# SCH_RP2040_2022-08-20.net
KiCad netlist of a schematic drawn in Altium Designer
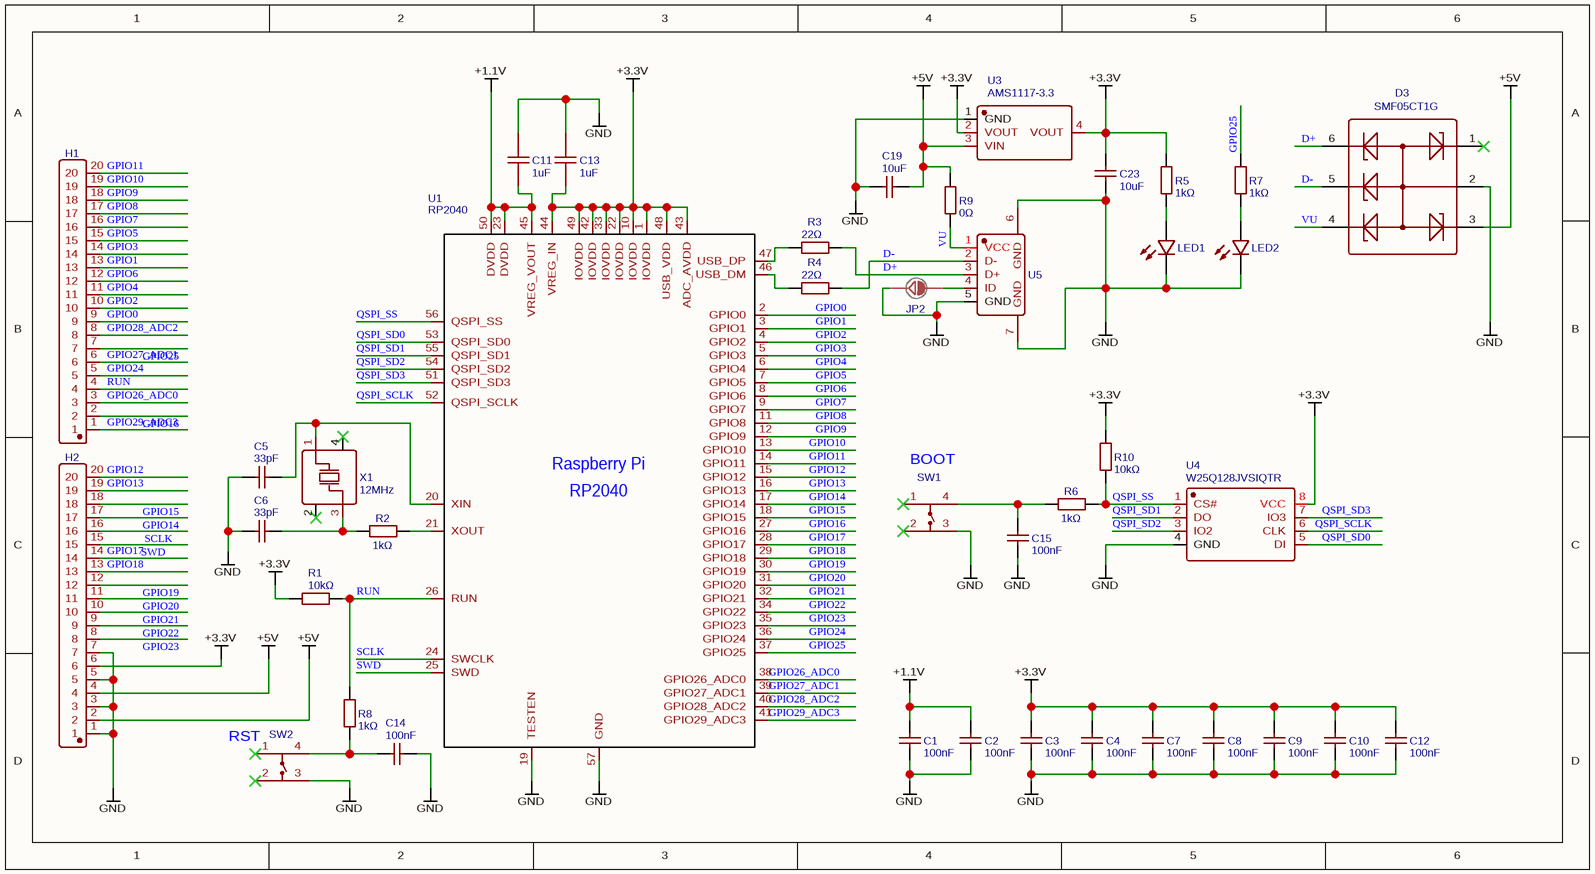
[diagram p0: SCH_RP2040_2022-08-20.schdoc]

(export (version "E")
  (design (tool "Eeschema 10.0.6"))
  (components
    (comp (ref "C1")
      (value "100nF")
      (fields
        (field (name "BOM_MANUFACTURER PART") "CL05B104KO5NNNC")
        (field (name "BOM_SUPPLIER PART") "C1525")
      )
      (libsource (lib "altium-import") (part "root_1_100nF_"))
    )
    (comp (ref "C2")
      (value "100nF")
      (fields
        (field (name "BOM_MANUFACTURER PART") "CL05B104KO5NNNC")
        (field (name "BOM_SUPPLIER PART") "C1525")
      )
      (libsource (lib "altium-import") (part "root_1_100nF_"))
    )
    (comp (ref "C3")
      (value "100nF")
      (fields
        (field (name "BOM_MANUFACTURER PART") "CL05B104KO5NNNC")
        (field (name "BOM_SUPPLIER PART") "C1525")
      )
      (libsource (lib "altium-import") (part "root_1_100nF_"))
    )
    (comp (ref "C4")
      (value "100nF")
      (fields
        (field (name "BOM_MANUFACTURER PART") "CL05B104KO5NNNC")
        (field (name "BOM_SUPPLIER PART") "C1525")
      )
      (libsource (lib "altium-import") (part "root_1_100nF_"))
    )
    (comp (ref "C5")
      (value "33pF")
      (fields
        (field (name "BOM_MANUFACTURER PART") "0402CG330J500NT")
        (field (name "BOM_SUPPLIER PART") "C1562")
      )
      (libsource (lib "altium-import") (part "root_0_33pF_"))
    )
    (comp (ref "C6")
      (value "33pF")
      (fields
        (field (name "BOM_MANUFACTURER PART") "0402CG330J500NT")
        (field (name "BOM_SUPPLIER PART") "C1562")
      )
      (libsource (lib "altium-import") (part "root_0_33pF_"))
    )
    (comp (ref "C7")
      (value "100nF")
      (fields
        (field (name "BOM_MANUFACTURER PART") "CL05B104KO5NNNC")
        (field (name "BOM_SUPPLIER PART") "C1525")
      )
      (libsource (lib "altium-import") (part "root_1_100nF_"))
    )
    (comp (ref "C8")
      (value "100nF")
      (fields
        (field (name "BOM_MANUFACTURER PART") "CL05B104KO5NNNC")
        (field (name "BOM_SUPPLIER PART") "C1525")
      )
      (libsource (lib "altium-import") (part "root_1_100nF_"))
    )
    (comp (ref "C9")
      (value "100nF")
      (fields
        (field (name "BOM_MANUFACTURER PART") "CL05B104KO5NNNC")
        (field (name "BOM_SUPPLIER PART") "C1525")
      )
      (libsource (lib "altium-import") (part "root_1_100nF_"))
    )
    (comp (ref "C10")
      (value "100nF")
      (fields
        (field (name "BOM_MANUFACTURER PART") "CL05B104KO5NNNC")
        (field (name "BOM_SUPPLIER PART") "C1525")
      )
      (libsource (lib "altium-import") (part "root_1_100nF_"))
    )
    (comp (ref "C11")
      (value "1uF")
      (fields
        (field (name "BOM_MANUFACTURER PART") "CL05A105KA5NQNC")
        (field (name "BOM_SUPPLIER PART") "C52923")
      )
      (libsource (lib "altium-import") (part "root_1_1uF_"))
    )
    (comp (ref "C12")
      (value "100nF")
      (fields
        (field (name "BOM_MANUFACTURER PART") "CL05B104KO5NNNC")
        (field (name "BOM_SUPPLIER PART") "C1525")
      )
      (libsource (lib "altium-import") (part "root_1_100nF_"))
    )
    (comp (ref "C13")
      (value "1uF")
      (fields
        (field (name "BOM_MANUFACTURER PART") "CL05A105KA5NQNC")
        (field (name "BOM_SUPPLIER PART") "C52923")
      )
      (libsource (lib "altium-import") (part "root_1_1uF_"))
    )
    (comp (ref "C14")
      (value "100nF")
      (fields
        (field (name "BOM_MANUFACTURER PART") "CL05B104KO5NNNC")
        (field (name "BOM_SUPPLIER PART") "C1525")
      )
      (libsource (lib "altium-import") (part "root_2_100nF_"))
    )
    (comp (ref "C15")
      (value "100nF")
      (fields
        (field (name "BOM_MANUFACTURER PART") "CL05B104KO5NNNC")
        (field (name "BOM_SUPPLIER PART") "C1525")
      )
      (libsource (lib "altium-import") (part "root_1_100nF_"))
    )
    (comp (ref "C19")
      (value "10uF")
      (fields
        (field (name "BOM_MANUFACTURER PART") "CL31A106KBHNNNE")
        (field (name "BOM_SUPPLIER PART") "C13585")
      )
      (libsource (lib "altium-import") (part "root_0_10uF_"))
    )
    (comp (ref "C23")
      (value "10uF")
      (fields
        (field (name "BOM_MANUFACTURER PART") "CL31A106KBHNNNE")
        (field (name "BOM_SUPPLIER PART") "C13585")
      )
      (libsource (lib "altium-import") (part "root_1_10uF_"))
    )
    (comp (ref "D3")
      (value "SMF05CT1G")
      (fields (field (name "BOM_SUPPLIER PART") "C15879"))
      (libsource (lib "altium-import") (part "root_0_SMF05CT1G_"))
    )
    (comp (ref "H1")
      (value "KH-2.54PH180-1X20P-L11.5")
      (fields (field (name "BOM_SUPPLIER PART") "C2905493") (field (name "CONTRIBUTOR") "LCSC"))
      (libsource (lib "altium-import") (part "root_2_KH-2.54PH180-1X20P-L11.5_"))
    )
    (comp (ref "H2")
      (value "KH-2.54PH180-1X20P-L11.5")
      (fields (field (name "BOM_SUPPLIER PART") "C2905493") (field (name "CONTRIBUTOR") "LCSC"))
      (libsource (lib "altium-import") (part "root_2_KH-2.54PH180-1X20P-L11.5_"))
    )
    (comp (ref "JP2")
      (value "JUMPER-SMT_2")
      (fields (field (name "CONTRIBUTOR") "Celeron"))
      (libsource (lib "altium-import") (part "root_0_JUMPER-SMT_2_"))
    )
    (comp (ref "LED1")
      (value "19-217/BHC-ZL1M2RY/3T")
      (fields (field (name "BOM_SUPPLIER PART") "C72041"))
      (libsource (lib "altium-import") (part "root_1_19-217/BHC-ZL1M2RY/3T_"))
    )
    (comp (ref "LED2")
      (value "19-217/BHC-ZL1M2RY/3T")
      (fields (field (name "BOM_SUPPLIER PART") "C72041"))
      (libsource (lib "altium-import") (part "root_1_19-217/BHC-ZL1M2RY/3T_"))
    )
    (comp (ref "R1")
      (value "10kΩ")
      (fields
        (field (name "BOM_MANUFACTURER PART") "0402WGF1002TCE")
        (field (name "BOM_SUPPLIER PART") "C25744")
      )
      (libsource (lib "altium-import") (part "root_2_10kΩ_"))
    )
    (comp (ref "R2")
      (value "1kΩ")
      (fields
        (field (name "BOM_MANUFACTURER PART") "0402WGF1001TCE")
        (field (name "BOM_SUPPLIER PART") "C11702")
      )
      (libsource (lib "altium-import") (part "root_0_1kΩ_"))
    )
    (comp (ref "R3")
      (value "22Ω")
      (fields
        (field (name "BOM_MANUFACTURER PART") "0402WGF220JTCE")
        (field (name "BOM_SUPPLIER PART") "C25092")
      )
      (libsource (lib "altium-import") (part "root_0_22Ω_"))
    )
    (comp (ref "R4")
      (value "22Ω")
      (fields
        (field (name "BOM_MANUFACTURER PART") "0402WGF220JTCE")
        (field (name "BOM_SUPPLIER PART") "C25092")
      )
      (libsource (lib "altium-import") (part "root_0_22Ω_"))
    )
    (comp (ref "R5")
      (value "1kΩ")
      (fields
        (field (name "BOM_MANUFACTURER PART") "0402WGF1001TCE")
        (field (name "BOM_SUPPLIER PART") "C11702")
      )
      (libsource (lib "altium-import") (part "root_1_1kΩ_"))
    )
    (comp (ref "R6")
      (value "1kΩ")
      (fields
        (field (name "BOM_MANUFACTURER PART") "0402WGF1001TCE")
        (field (name "BOM_SUPPLIER PART") "C11702")
      )
      (libsource (lib "altium-import") (part "root_0_1kΩ_"))
    )
    (comp (ref "R7")
      (value "1kΩ")
      (fields
        (field (name "BOM_MANUFACTURER PART") "0402WGF1001TCE")
        (field (name "BOM_SUPPLIER PART") "C11702")
      )
      (libsource (lib "altium-import") (part "root_1_1kΩ_"))
    )
    (comp (ref "R8")
      (value "1kΩ")
      (fields
        (field (name "BOM_MANUFACTURER PART") "0402WGF1001TCE")
        (field (name "BOM_SUPPLIER PART") "C11702")
      )
      (libsource (lib "altium-import") (part "root_1_1kΩ_"))
    )
    (comp (ref "R9")
      (value "0Ω")
      (fields
        (field (name "BOM_MANUFACTURER PART") "0603WAF0000T5E")
        (field (name "BOM_SUPPLIER PART") "C21189")
      )
      (libsource (lib "altium-import") (part "root_1_0Ω_"))
    )
    (comp (ref "R10")
      (value "10kΩ")
      (fields
        (field (name "BOM_MANUFACTURER PART") "0402WGF1002TCE")
        (field (name "BOM_SUPPLIER PART") "C25744")
      )
      (libsource (lib "altium-import") (part "root_1_10kΩ_"))
    )
    (comp (ref "SW1")
      (value "TD-1182SA-2.0H-250")
      (fields (field (name "BOM_SUPPLIER PART") "C2905178") (field (name "CONTRIBUTOR") "LCSC"))
      (libsource (lib "altium-import") (part "root_0_TD-1182SA-2.0H-250_"))
    )
    (comp (ref "SW2")
      (value "TD-1182SA-2.0H-250")
      (fields (field (name "BOM_SUPPLIER PART") "C2905178") (field (name "CONTRIBUTOR") "LCSC"))
      (libsource (lib "altium-import") (part "root_0_TD-1182SA-2.0H-250_"))
    )
    (comp (ref "U1")
      (value "RP2040")
      (fields (field (name "BOM_SUPPLIER PART") "C2040") (field (name "CONTRIBUTOR") "LCSC"))
      (libsource (lib "altium-import") (part "root_0_RP2040_"))
    )
    (comp (ref "U3")
      (value "AMS1117-3.3")
      (fields (field (name "BOM_SUPPLIER PART") "C6186"))
      (libsource (lib "altium-import") (part "root_0_AMS1117-3.3_"))
    )
    (comp (ref "U4")
      (value "W25Q128JVSIQTR")
      (fields (field (name "BOM_SUPPLIER PART") "C97521"))
      (libsource (lib "altium-import") (part "root_0_W25Q128JVSIQTR_"))
    )
    (comp (ref "U5")
      (value "U253-051N-4BH89-S2S")
      (fields (field (name "BOM_SUPPLIER PART") "C2880620") (field (name "CONTRIBUTOR") "LCSC"))
      (libsource (lib "altium-import") (part "root_0_U253-051N-4BH89-S2S_"))
    )
    (comp (ref "X1")
      (value "12MHz")
      (fields
        (field (name "BOM_MANUFACTURER PART") "X322512MSB4SI")
        (field (name "BOM_SUPPLIER PART") "C9002")
      )
      (libsource (lib "altium-import") (part "root_3_12MHz_"))
    )
  )
  (nets
    (net (code "1") (name "+1.1V") (class "Default")
      (node (ref "C1") (pin "2") (pinfunction "2_2") (pintype "passive"))
      (node (ref "C11") (pin "1") (pinfunction "1_1") (pintype "passive"))
      (node (ref "C2") (pin "2") (pinfunction "2_2") (pintype "passive"))
      (node (ref "U1") (pin "23") (pinfunction "DVDD_23") (pintype "passive"))
      (node (ref "U1") (pin "45") (pinfunction "VREG_VOUT_45") (pintype "passive"))
      (node (ref "U1") (pin "50") (pinfunction "DVDD_50") (pintype "passive"))
    )
    (net (code "2") (name "+3.3V") (class "Default")
      (node (ref "C10") (pin "2") (pinfunction "2_2") (pintype "passive"))
      (node (ref "C12") (pin "2") (pinfunction "2_2") (pintype "passive"))
      (node (ref "C13") (pin "1") (pinfunction "1_1") (pintype "passive"))
      (node (ref "C23") (pin "2") (pinfunction "2_2") (pintype "passive"))
      (node (ref "C3") (pin "2") (pinfunction "2_2") (pintype "passive"))
      (node (ref "C4") (pin "2") (pinfunction "2_2") (pintype "passive"))
      (node (ref "C7") (pin "2") (pinfunction "2_2") (pintype "passive"))
      (node (ref "C8") (pin "2") (pinfunction "2_2") (pintype "passive"))
      (node (ref "C9") (pin "2") (pinfunction "2_2") (pintype "passive"))
      (node (ref "H2") (pin "6") (pinfunction "6_6") (pintype "passive"))
      (node (ref "R1") (pin "2") (pinfunction "2_2") (pintype "passive"))
      (node (ref "R10") (pin "2") (pinfunction "2_2") (pintype "passive"))
      (node (ref "R5") (pin "2") (pinfunction "2_2") (pintype "passive"))
      (node (ref "U1") (pin "1") (pinfunction "IOVDD_1") (pintype "passive"))
      (node (ref "U1") (pin "10") (pinfunction "IOVDD_10") (pintype "passive"))
      (node (ref "U1") (pin "22") (pinfunction "IOVDD_22") (pintype "passive"))
      (node (ref "U1") (pin "33") (pinfunction "IOVDD_33") (pintype "passive"))
      (node (ref "U1") (pin "42") (pinfunction "IOVDD_42") (pintype "passive"))
      (node (ref "U1") (pin "43") (pinfunction "ADC_AVDD_43") (pintype "passive"))
      (node (ref "U1") (pin "44") (pinfunction "VREG_IN_44") (pintype "passive"))
      (node (ref "U1") (pin "48") (pinfunction "USB_VDD_48") (pintype "passive"))
      (node (ref "U1") (pin "49") (pinfunction "IOVDD_49") (pintype "passive"))
      (node (ref "U3") (pin "2") (pinfunction "VOUT_2") (pintype "passive"))
      (node (ref "U3") (pin "4") (pinfunction "VOUT_4") (pintype "passive"))
      (node (ref "U4") (pin "8") (pinfunction "VCC_8") (pintype "passive"))
    )
    (net (code "3") (name "+5V") (class "Default")
      (node (ref "C19") (pin "2") (pinfunction "2_2") (pintype "passive"))
      (node (ref "D3") (pin "3") (pinfunction "3_3") (pintype "passive"))
      (node (ref "H2") (pin "2") (pinfunction "2_2") (pintype "passive"))
      (node (ref "H2") (pin "4") (pinfunction "4_4") (pintype "passive"))
      (node (ref "R9") (pin "2") (pinfunction "2_2") (pintype "passive"))
      (node (ref "U3") (pin "3") (pinfunction "VIN_3") (pintype "passive"))
    )
    (net (code "4") (name "/D+") (class "Default")
      (node (ref "D3") (pin "6") (pinfunction "6_6") (pintype "passive"))
      (node (ref "R3") (pin "1") (pinfunction "1_1") (pintype "passive"))
      (node (ref "U5") (pin "3") (pinfunction "D+_3") (pintype "passive"))
    )
    (net (code "5") (name "/D-") (class "Default")
      (node (ref "D3") (pin "5") (pinfunction "5_5") (pintype "passive"))
      (node (ref "R4") (pin "1") (pinfunction "1_1") (pintype "passive"))
      (node (ref "U5") (pin "2") (pinfunction "D-_2") (pintype "passive"))
    )
    (net (code "6") (name "/GPIO0") (class "Default")
      (node (ref "H1") (pin "9") (pinfunction "9_9") (pintype "passive"))
      (node (ref "U1") (pin "2") (pinfunction "GPIO0_2") (pintype "passive"))
    )
    (net (code "7") (name "/GPIO1") (class "Default")
      (node (ref "H1") (pin "13") (pinfunction "13_13") (pintype "passive"))
      (node (ref "U1") (pin "3") (pinfunction "GPIO1_3") (pintype "passive"))
    )
    (net (code "8") (name "/GPIO2") (class "Default")
      (node (ref "H1") (pin "10") (pinfunction "10_10") (pintype "passive"))
      (node (ref "U1") (pin "4") (pinfunction "GPIO2_4") (pintype "passive"))
    )
    (net (code "9") (name "/GPIO3") (class "Default")
      (node (ref "H1") (pin "14") (pinfunction "14_14") (pintype "passive"))
      (node (ref "U1") (pin "5") (pinfunction "GPIO3_5") (pintype "passive"))
    )
    (net (code "10") (name "/GPIO4") (class "Default")
      (node (ref "H1") (pin "11") (pinfunction "11_11") (pintype "passive"))
      (node (ref "U1") (pin "6") (pinfunction "GPIO4_6") (pintype "passive"))
    )
    (net (code "11") (name "/GPIO5") (class "Default")
      (node (ref "H1") (pin "15") (pinfunction "15_15") (pintype "passive"))
      (node (ref "U1") (pin "7") (pinfunction "GPIO5_7") (pintype "passive"))
    )
    (net (code "12") (name "/GPIO6") (class "Default")
      (node (ref "H1") (pin "12") (pinfunction "12_12") (pintype "passive"))
      (node (ref "U1") (pin "8") (pinfunction "GPIO6_8") (pintype "passive"))
    )
    (net (code "13") (name "/GPIO7") (class "Default")
      (node (ref "H1") (pin "16") (pinfunction "16_16") (pintype "passive"))
      (node (ref "U1") (pin "9") (pinfunction "GPIO7_9") (pintype "passive"))
    )
    (net (code "14") (name "/GPIO8") (class "Default")
      (node (ref "H1") (pin "17") (pinfunction "17_17") (pintype "passive"))
      (node (ref "U1") (pin "11") (pinfunction "GPIO8_11") (pintype "passive"))
    )
    (net (code "15") (name "/GPIO9") (class "Default")
      (node (ref "H1") (pin "18") (pinfunction "18_18") (pintype "passive"))
      (node (ref "U1") (pin "12") (pinfunction "GPIO9_12") (pintype "passive"))
    )
    (net (code "16") (name "/GPIO10") (class "Default")
      (node (ref "H1") (pin "19") (pinfunction "19_19") (pintype "passive"))
      (node (ref "U1") (pin "13") (pinfunction "GPIO10_13") (pintype "passive"))
    )
    (net (code "17") (name "/GPIO11") (class "Default")
      (node (ref "H1") (pin "20") (pinfunction "20_20") (pintype "passive"))
      (node (ref "U1") (pin "14") (pinfunction "GPIO11_14") (pintype "passive"))
    )
    (net (code "18") (name "/GPIO12") (class "Default")
      (node (ref "H2") (pin "20") (pinfunction "20_20") (pintype "passive"))
      (node (ref "U1") (pin "15") (pinfunction "GPIO12_15") (pintype "passive"))
    )
    (net (code "19") (name "/GPIO13") (class "Default")
      (node (ref "H2") (pin "19") (pinfunction "19_19") (pintype "passive"))
      (node (ref "U1") (pin "16") (pinfunction "GPIO13_16") (pintype "passive"))
    )
    (net (code "20") (name "/GPIO14") (class "Default")
      (node (ref "H2") (pin "17") (pinfunction "17_17") (pintype "passive"))
      (node (ref "U1") (pin "17") (pinfunction "GPIO14_17") (pintype "passive"))
    )
    (net (code "21") (name "/GPIO15") (class "Default")
      (node (ref "H2") (pin "18") (pinfunction "18_18") (pintype "passive"))
      (node (ref "U1") (pin "18") (pinfunction "GPIO15_18") (pintype "passive"))
    )
    (net (code "22") (name "/GPIO16") (class "Default")
      (node (ref "H1") (pin "2") (pinfunction "2_2") (pintype "passive"))
      (node (ref "U1") (pin "27") (pinfunction "GPIO16_27") (pintype "passive"))
    )
    (net (code "23") (name "/GPIO17") (class "Default")
      (node (ref "H2") (pin "14") (pinfunction "14_14") (pintype "passive"))
      (node (ref "U1") (pin "28") (pinfunction "GPIO17_28") (pintype "passive"))
    )
    (net (code "24") (name "/GPIO18") (class "Default")
      (node (ref "H2") (pin "13") (pinfunction "13_13") (pintype "passive"))
      (node (ref "U1") (pin "29") (pinfunction "GPIO18_29") (pintype "passive"))
    )
    (net (code "25") (name "/GPIO19") (class "Default")
      (node (ref "H2") (pin "12") (pinfunction "12_12") (pintype "passive"))
      (node (ref "U1") (pin "30") (pinfunction "GPIO19_30") (pintype "passive"))
    )
    (net (code "26") (name "/GPIO20") (class "Default")
      (node (ref "H2") (pin "11") (pinfunction "11_11") (pintype "passive"))
      (node (ref "U1") (pin "31") (pinfunction "GPIO20_31") (pintype "passive"))
    )
    (net (code "27") (name "/GPIO21") (class "Default")
      (node (ref "H2") (pin "10") (pinfunction "10_10") (pintype "passive"))
      (node (ref "U1") (pin "32") (pinfunction "GPIO21_32") (pintype "passive"))
    )
    (net (code "28") (name "/GPIO22") (class "Default")
      (node (ref "H2") (pin "9") (pinfunction "9_9") (pintype "passive"))
      (node (ref "U1") (pin "34") (pinfunction "GPIO22_34") (pintype "passive"))
    )
    (net (code "29") (name "/GPIO23") (class "Default")
      (node (ref "H2") (pin "8") (pinfunction "8_8") (pintype "passive"))
      (node (ref "U1") (pin "35") (pinfunction "GPIO23_35") (pintype "passive"))
    )
    (net (code "30") (name "/GPIO24") (class "Default")
      (node (ref "H1") (pin "5") (pinfunction "5_5") (pintype "passive"))
      (node (ref "U1") (pin "36") (pinfunction "GPIO24_36") (pintype "passive"))
    )
    (net (code "31") (name "/GPIO25") (class "Default")
      (node (ref "H1") (pin "7") (pinfunction "7_7") (pintype "passive"))
      (node (ref "R7") (pin "2") (pinfunction "2_2") (pintype "passive"))
      (node (ref "U1") (pin "37") (pinfunction "GPIO25_37") (pintype "passive"))
    )
    (net (code "32") (name "/GPIO26_ADC0") (class "Default")
      (node (ref "H1") (pin "3") (pinfunction "3_3") (pintype "passive"))
      (node (ref "U1") (pin "38") (pinfunction "GPIO26_ADC0_38") (pintype "passive"))
    )
    (net (code "33") (name "/GPIO27_ADC1") (class "Default")
      (node (ref "H1") (pin "6") (pinfunction "6_6") (pintype "passive"))
      (node (ref "U1") (pin "39") (pinfunction "GPIO27_ADC1_39") (pintype "passive"))
    )
    (net (code "34") (name "/GPIO28_ADC2") (class "Default")
      (node (ref "H1") (pin "8") (pinfunction "8_8") (pintype "passive"))
      (node (ref "U1") (pin "40") (pinfunction "GPIO28_ADC2_40") (pintype "passive"))
    )
    (net (code "35") (name "/GPIO29_ADC3") (class "Default")
      (node (ref "H1") (pin "1") (pinfunction "1_1") (pintype "passive"))
      (node (ref "U1") (pin "41") (pinfunction "GPIO29_ADC3_41") (pintype "passive"))
    )
    (net (code "36") (name "/QSPI_SCLK") (class "Default")
      (node (ref "U1") (pin "52") (pinfunction "QSPI_SCLK_52") (pintype "passive"))
      (node (ref "U4") (pin "6") (pinfunction "CLK_6") (pintype "passive"))
    )
    (net (code "37") (name "/QSPI_SD0") (class "Default")
      (node (ref "U1") (pin "53") (pinfunction "QSPI_SD0_53") (pintype "passive"))
      (node (ref "U4") (pin "5") (pinfunction "DI_5") (pintype "passive"))
    )
    (net (code "38") (name "/QSPI_SD1") (class "Default")
      (node (ref "U1") (pin "55") (pinfunction "QSPI_SD1_55") (pintype "passive"))
      (node (ref "U4") (pin "2") (pinfunction "DO_2") (pintype "passive"))
    )
    (net (code "39") (name "/QSPI_SD2") (class "Default")
      (node (ref "U1") (pin "54") (pinfunction "QSPI_SD2_54") (pintype "passive"))
      (node (ref "U4") (pin "3") (pinfunction "IO2_3") (pintype "passive"))
    )
    (net (code "40") (name "/QSPI_SD3") (class "Default")
      (node (ref "U1") (pin "51") (pinfunction "QSPI_SD3_51") (pintype "passive"))
      (node (ref "U4") (pin "7") (pinfunction "IO3_7") (pintype "passive"))
    )
    (net (code "41") (name "/QSPI_SS") (class "Default")
      (node (ref "R10") (pin "1") (pinfunction "1_1") (pintype "passive"))
      (node (ref "R6") (pin "2") (pinfunction "2_2") (pintype "passive"))
      (node (ref "U1") (pin "56") (pinfunction "QSPI_SS_56") (pintype "passive"))
      (node (ref "U4") (pin "1") (pinfunction "CS#_1") (pintype "passive"))
    )
    (net (code "42") (name "/RUN") (class "Default")
      (node (ref "H1") (pin "4") (pinfunction "4_4") (pintype "passive"))
      (node (ref "R1") (pin "1") (pinfunction "1_1") (pintype "passive"))
      (node (ref "R8") (pin "2") (pinfunction "2_2") (pintype "passive"))
      (node (ref "U1") (pin "26") (pinfunction "RUN_26") (pintype "passive"))
    )
    (net (code "43") (name "/SCLK") (class "Default")
      (node (ref "H2") (pin "16") (pinfunction "16_16") (pintype "passive"))
      (node (ref "U1") (pin "24") (pinfunction "SWCLK_24") (pintype "passive"))
    )
    (net (code "44") (name "/SWD") (class "Default")
      (node (ref "H2") (pin "15") (pinfunction "15_15") (pintype "passive"))
      (node (ref "U1") (pin "25") (pinfunction "SWD_25") (pintype "passive"))
    )
    (net (code "45") (name "/VU") (class "Default")
      (node (ref "D3") (pin "4") (pinfunction "4_4") (pintype "passive"))
      (node (ref "R9") (pin "1") (pinfunction "1_1") (pintype "passive"))
      (node (ref "U5") (pin "1") (pinfunction "VCC_1") (pintype "passive"))
    )
    (net (code "46") (name "GND") (class "Default")
      (node (ref "C1") (pin "1") (pinfunction "1_1") (pintype "passive"))
      (node (ref "C10") (pin "1") (pinfunction "1_1") (pintype "passive"))
      (node (ref "C11") (pin "2") (pinfunction "2_2") (pintype "passive"))
      (node (ref "C12") (pin "1") (pinfunction "1_1") (pintype "passive"))
      (node (ref "C13") (pin "2") (pinfunction "2_2") (pintype "passive"))
      (node (ref "C14") (pin "1") (pinfunction "1_1") (pintype "passive"))
      (node (ref "C15") (pin "1") (pinfunction "1_1") (pintype "passive"))
      (node (ref "C19") (pin "1") (pinfunction "1_1") (pintype "passive"))
      (node (ref "C2") (pin "1") (pinfunction "1_1") (pintype "passive"))
      (node (ref "C23") (pin "1") (pinfunction "1_1") (pintype "passive"))
      (node (ref "C3") (pin "1") (pinfunction "1_1") (pintype "passive"))
      (node (ref "C4") (pin "1") (pinfunction "1_1") (pintype "passive"))
      (node (ref "C5") (pin "1") (pinfunction "1_1") (pintype "passive"))
      (node (ref "C6") (pin "1") (pinfunction "1_1") (pintype "passive"))
      (node (ref "C7") (pin "1") (pinfunction "1_1") (pintype "passive"))
      (node (ref "C8") (pin "1") (pinfunction "1_1") (pintype "passive"))
      (node (ref "C9") (pin "1") (pinfunction "1_1") (pintype "passive"))
      (node (ref "D3") (pin "2") (pinfunction "2_2") (pintype "passive"))
      (node (ref "H2") (pin "1") (pinfunction "1_1") (pintype "passive"))
      (node (ref "H2") (pin "3") (pinfunction "3_3") (pintype "passive"))
      (node (ref "H2") (pin "5") (pinfunction "5_5") (pintype "passive"))
      (node (ref "H2") (pin "7") (pinfunction "7_7") (pintype "passive"))
      (node (ref "JP2") (pin "1") (pinfunction "1_1") (pintype "passive"))
      (node (ref "LED1") (pin "2") (pinfunction "C_2") (pintype "passive"))
      (node (ref "LED2") (pin "2") (pinfunction "C_2") (pintype "passive"))
      (node (ref "SW1") (pin "3") (pinfunction "3_3") (pintype "passive"))
      (node (ref "SW2") (pin "3") (pinfunction "3_3") (pintype "passive"))
      (node (ref "U1") (pin "19") (pinfunction "TESTEN_19") (pintype "passive"))
      (node (ref "U1") (pin "57") (pinfunction "GND_57") (pintype "passive"))
      (node (ref "U3") (pin "1") (pinfunction "GND_1") (pintype "passive"))
      (node (ref "U4") (pin "4") (pinfunction "GND_4") (pintype "passive"))
      (node (ref "U5") (pin "5") (pinfunction "GND_5") (pintype "passive"))
      (node (ref "U5") (pin "6") (pinfunction "GND_6") (pintype "passive"))
      (node (ref "U5") (pin "7") (pinfunction "GND_7") (pintype "passive"))
    )
    (net (code "47") (name "Net-(C14-Pad2)") (class "Default")
      (node (ref "C14") (pin "2") (pinfunction "2_2") (pintype "passive"))
      (node (ref "R8") (pin "1") (pinfunction "1_1") (pintype "passive"))
      (node (ref "SW2") (pin "4") (pinfunction "4_4") (pintype "passive"))
    )
    (net (code "48") (name "Net-(C15-Pad2)") (class "Default")
      (node (ref "C15") (pin "2") (pinfunction "2_2") (pintype "passive"))
      (node (ref "R6") (pin "1") (pinfunction "1_1") (pintype "passive"))
      (node (ref "SW1") (pin "4") (pinfunction "4_4") (pintype "passive"))
    )
    (net (code "49") (name "Net-(LED1-A)") (class "Default")
      (node (ref "LED1") (pin "1") (pinfunction "A_1") (pintype "passive"))
      (node (ref "R5") (pin "1") (pinfunction "1_1") (pintype "passive"))
    )
    (net (code "50") (name "Net-(LED2-A)") (class "Default")
      (node (ref "LED2") (pin "1") (pinfunction "A_1") (pintype "passive"))
      (node (ref "R7") (pin "1") (pinfunction "1_1") (pintype "passive"))
    )
    (net (code "51") (name "Net-(U1-USB_DM)") (class "Default")
      (node (ref "R4") (pin "2") (pinfunction "2_2") (pintype "passive"))
      (node (ref "U1") (pin "46") (pinfunction "USB_DM_46") (pintype "passive"))
    )
    (net (code "52") (name "Net-(U1-USB_DP)") (class "Default")
      (node (ref "R3") (pin "2") (pinfunction "2_2") (pintype "passive"))
      (node (ref "U1") (pin "47") (pinfunction "USB_DP_47") (pintype "passive"))
    )
    (net (code "53") (name "Net-(U1-XIN)") (class "Default")
      (node (ref "C5") (pin "2") (pinfunction "2_2") (pintype "passive"))
      (node (ref "U1") (pin "20") (pinfunction "XIN_20") (pintype "passive"))
      (node (ref "X1") (pin "1") (pinfunction "OSC1_1") (pintype "passive"))
    )
    (net (code "54") (name "Net-(U1-XOUT)") (class "Default")
      (node (ref "R2") (pin "2") (pinfunction "2_2") (pintype "passive"))
      (node (ref "U1") (pin "21") (pinfunction "XOUT_21") (pintype "passive"))
    )
    (net (code "55") (name "Net-(U5-ID)") (class "Default")
      (node (ref "JP2") (pin "2") (pinfunction "2_2") (pintype "passive"))
      (node (ref "U5") (pin "4") (pinfunction "ID_4") (pintype "passive"))
    )
    (net (code "56") (name "Net-(X1-OSC2)") (class "Default")
      (node (ref "C6") (pin "2") (pinfunction "2_2") (pintype "passive"))
      (node (ref "R2") (pin "1") (pinfunction "1_1") (pintype "passive"))
      (node (ref "X1") (pin "3") (pinfunction "OSC2_3") (pintype "passive"))
    )
    (net (code "57") (name "unconnected-(D3-Pad1)") (class "Default")
      (node (ref "D3") (pin "1") (pinfunction "1_1") (pintype "passive+no_connect"))
    )
    (net (code "58") (name "unconnected-(SW1-Pad1)") (class "Default")
      (node (ref "SW1") (pin "1") (pinfunction "1_1") (pintype "passive+no_connect"))
    )
    (net (code "59") (name "unconnected-(SW1-Pad2)") (class "Default")
      (node (ref "SW1") (pin "2") (pinfunction "2_2") (pintype "passive+no_connect"))
    )
    (net (code "60") (name "unconnected-(SW2-Pad1)") (class "Default")
      (node (ref "SW2") (pin "1") (pinfunction "1_1") (pintype "passive+no_connect"))
    )
    (net (code "61") (name "unconnected-(SW2-Pad2)") (class "Default")
      (node (ref "SW2") (pin "2") (pinfunction "2_2") (pintype "passive+no_connect"))
    )
    (net (code "62") (name "unconnected-(X1-GND-Pad2)") (class "Default")
      (node (ref "X1") (pin "2") (pinfunction "GND_2") (pintype "passive+no_connect"))
    )
    (net (code "63") (name "unconnected-(X1-GND-Pad4)") (class "Default")
      (node (ref "X1") (pin "4") (pinfunction "GND_4") (pintype "passive+no_connect"))
    )
  )
)
